# USBUART_CP2102.net
KiCad netlist of a schematic drawn in Altium Designer
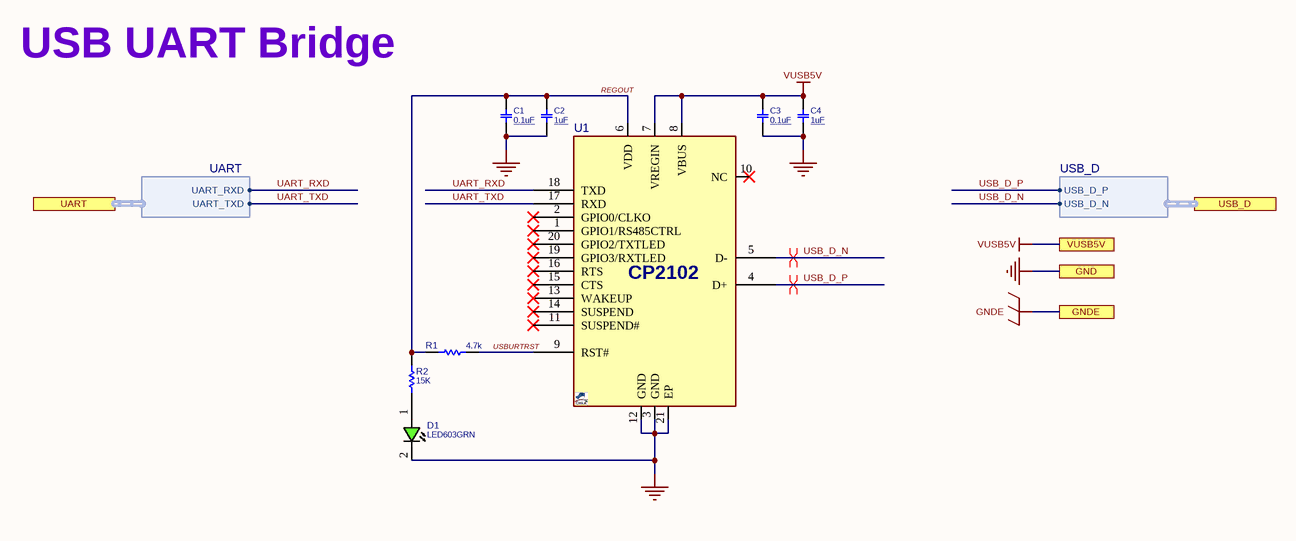
[diagram p0: USBUART_CP2102.SchDoc]

(export (version "E")
  (design (tool "Eeschema 10.0.6"))
  (components
    (comp (ref "C1")
      (value "0.1uF")
      (footprint "C0402")
      (description "CAP, MLCC, 1nF, 50V, C0G, 10%, 0402")
      (fields (field (name "MANF") "Murata"))
      (libsource (lib "mlcc_smd_passive") (part "CAP_SMD_MLCC"))
    )
    (comp (ref "C2")
      (value "1uF")
      (footprint "C0402")
      (description "CAP, MLCC, 1nF, 50V, C0G, 10%, 0402")
      (fields (field (name "MANF") "Murata"))
      (libsource (lib "mlcc_smd_passive") (part "CAP_SMD_MLCC"))
    )
    (comp (ref "C3")
      (value "0.1uF")
      (footprint "C0402")
      (description "CAP, MLCC, 1nF, 50V, C0G, 10%, 0402")
      (fields (field (name "MANF") "Murata"))
      (libsource (lib "mlcc_smd_passive") (part "CAP_SMD_MLCC"))
    )
    (comp (ref "C4")
      (value "1uF")
      (footprint "C0402")
      (description "CAP, MLCC, 1nF, 50V, C0G, 10%, 0402")
      (fields (field (name "MANF") "Murata"))
      (libsource (lib "mlcc_smd_passive") (part "CAP_SMD_MLCC"))
    )
    (comp (ref "D1")
      (value "LED603GRN")
      (footprint "LED0603GRN")
      (description "LED, SMD, 0603, GREEN")
      (fields (field (name "MANF") "Kingbright") (field (name "MANF_P#") "APT1608SGC"))
      (libsource (lib "led(diode)") (part "LED_SMD_0603_GRN"))
    )
    (comp (ref "R1")
      (value "4.7k")
      (footprint "R0402")
      (description "RESISTOR, SMD")
      (libsource (lib "res_smd_passive") (part "RES_SMD"))
    )
    (comp (ref "R2")
      (value "15K")
      (footprint "R0402")
      (description "RESISTOR, SMD")
      (libsource (lib "res_smd_passive") (part "RES_SMD"))
    )
    (comp (ref "U1")
      (value "CP2102")
      (footprint "QFN50_20T_3X3")
      (description "USB-UART BRIDGE")
      (fields (field (name "MANF") "SILICON LABS") (field (name "MANF_1") "MANF"))
      (libsource (lib "usbic") (part "CP2102_QFN20"))
    )
  )
  (nets
    (net (code "3") (name "/REGOUT") (class "Default")
      (node (ref "C1") (pin "1") (pinfunction "1_1") (pintype "passive"))
      (node (ref "C2") (pin "1") (pinfunction "1_1") (pintype "passive"))
      (node (ref "R1") (pin "2") (pinfunction "2_2") (pintype "passive"))
      (node (ref "R2") (pin "1") (pinfunction "1_1") (pintype "passive"))
      (node (ref "U1") (pin "6") (pinfunction "VDD_6") (pintype "passive"))
    )
    (net (code "4") (name "/UART_RXD") (class "Default")
      (node (ref "U1") (pin "18") (pinfunction "TXD_18") (pintype "passive"))
    )
    (net (code "5") (name "/UART_TXD") (class "Default")
      (node (ref "U1") (pin "17") (pinfunction "RXD_17") (pintype "passive"))
    )
    (net (code "6") (name "/USBURTRST") (class "Default")
      (node (ref "R1") (pin "1") (pinfunction "1_1") (pintype "passive"))
      (node (ref "U1") (pin "9") (pinfunction "RST#_9") (pintype "passive"))
    )
    (net (code "7") (name "/USB_D_N") (class "Default")
      (node (ref "U1") (pin "5") (pinfunction "D-_5") (pintype "passive"))
    )
    (net (code "8") (name "/USB_D_P") (class "Default")
      (node (ref "U1") (pin "4") (pinfunction "D+_4") (pintype "passive"))
    )
    (net (code "11") (name "GND") (class "Default")
      (node (ref "C1") (pin "2") (pinfunction "2_2") (pintype "passive"))
      (node (ref "C2") (pin "2") (pinfunction "2_2") (pintype "passive"))
      (node (ref "C3") (pin "2") (pinfunction "2_2") (pintype "passive"))
      (node (ref "C4") (pin "2") (pinfunction "2_2") (pintype "passive"))
      (node (ref "D1") (pin "2") (pinfunction "CATHODE_2") (pintype "passive"))
      (node (ref "U1") (pin "12") (pinfunction "GND_12") (pintype "passive"))
      (node (ref "U1") (pin "21") (pinfunction "EP_21") (pintype "passive"))
      (node (ref "U1") (pin "3") (pinfunction "GND_3") (pintype "passive"))
    )
    (net (code "13") (name "Net-(D1-ANODE)") (class "Default")
      (node (ref "D1") (pin "1") (pinfunction "ANODE_1") (pintype "passive"))
      (node (ref "R2") (pin "2") (pinfunction "2_2") (pintype "passive"))
    )
    (net (code "14") (name "VUSB5V") (class "Default")
      (node (ref "C3") (pin "1") (pinfunction "1_1") (pintype "passive"))
      (node (ref "C4") (pin "1") (pinfunction "1_1") (pintype "passive"))
      (node (ref "U1") (pin "7") (pinfunction "VREGIN_7") (pintype "passive"))
      (node (ref "U1") (pin "8") (pinfunction "VBUS_8") (pintype "passive"))
    )
    (net (code "15") (name "unconnected-(U1-CTS-Pad15)") (class "Default")
      (node (ref "U1") (pin "15") (pinfunction "CTS_15") (pintype "passive+no_connect"))
    )
    (net (code "16") (name "unconnected-(U1-GPIO0{slash}CLKO-Pad2)") (class "Default")
      (node (ref "U1") (pin "2") (pinfunction "GPIO0/CLKO_2") (pintype "passive+no_connect"))
    )
    (net (code "17") (name "unconnected-(U1-GPIO1{slash}RS485CTRL-Pad1)") (class "Default")
      (node (ref "U1") (pin "1") (pinfunction "GPIO1/RS485CTRL_1") (pintype "passive+no_connect"))
    )
    (net (code "18") (name "unconnected-(U1-GPIO2{slash}TXTLED-Pad20)") (class "Default")
      (node (ref "U1") (pin "20") (pinfunction "GPIO2/TXTLED_20") (pintype "passive+no_connect"))
    )
    (net (code "19") (name "unconnected-(U1-GPIO3{slash}RXTLED-Pad19)") (class "Default")
      (node (ref "U1") (pin "19") (pinfunction "GPIO3/RXTLED_19") (pintype "passive+no_connect"))
    )
    (net (code "20") (name "unconnected-(U1-NC-Pad10)") (class "Default")
      (node (ref "U1") (pin "10") (pinfunction "NC_10") (pintype "passive+no_connect"))
    )
    (net (code "21") (name "unconnected-(U1-RTS-Pad16)") (class "Default")
      (node (ref "U1") (pin "16") (pinfunction "RTS_16") (pintype "passive+no_connect"))
    )
    (net (code "22") (name "unconnected-(U1-SUSPEND#-Pad11)") (class "Default")
      (node (ref "U1") (pin "11") (pinfunction "SUSPEND#_11") (pintype "passive+no_connect"))
    )
    (net (code "23") (name "unconnected-(U1-SUSPEND-Pad14)") (class "Default")
      (node (ref "U1") (pin "14") (pinfunction "SUSPEND_14") (pintype "passive+no_connect"))
    )
    (net (code "24") (name "unconnected-(U1-WAKEUP-Pad13)") (class "Default")
      (node (ref "U1") (pin "13") (pinfunction "WAKEUP_13") (pintype "passive+no_connect"))
    )
  )
)
